# CSI2-TX2-XAVIER_Rev01.net
KiCad netlist of a schematic drawn in Altium Designer
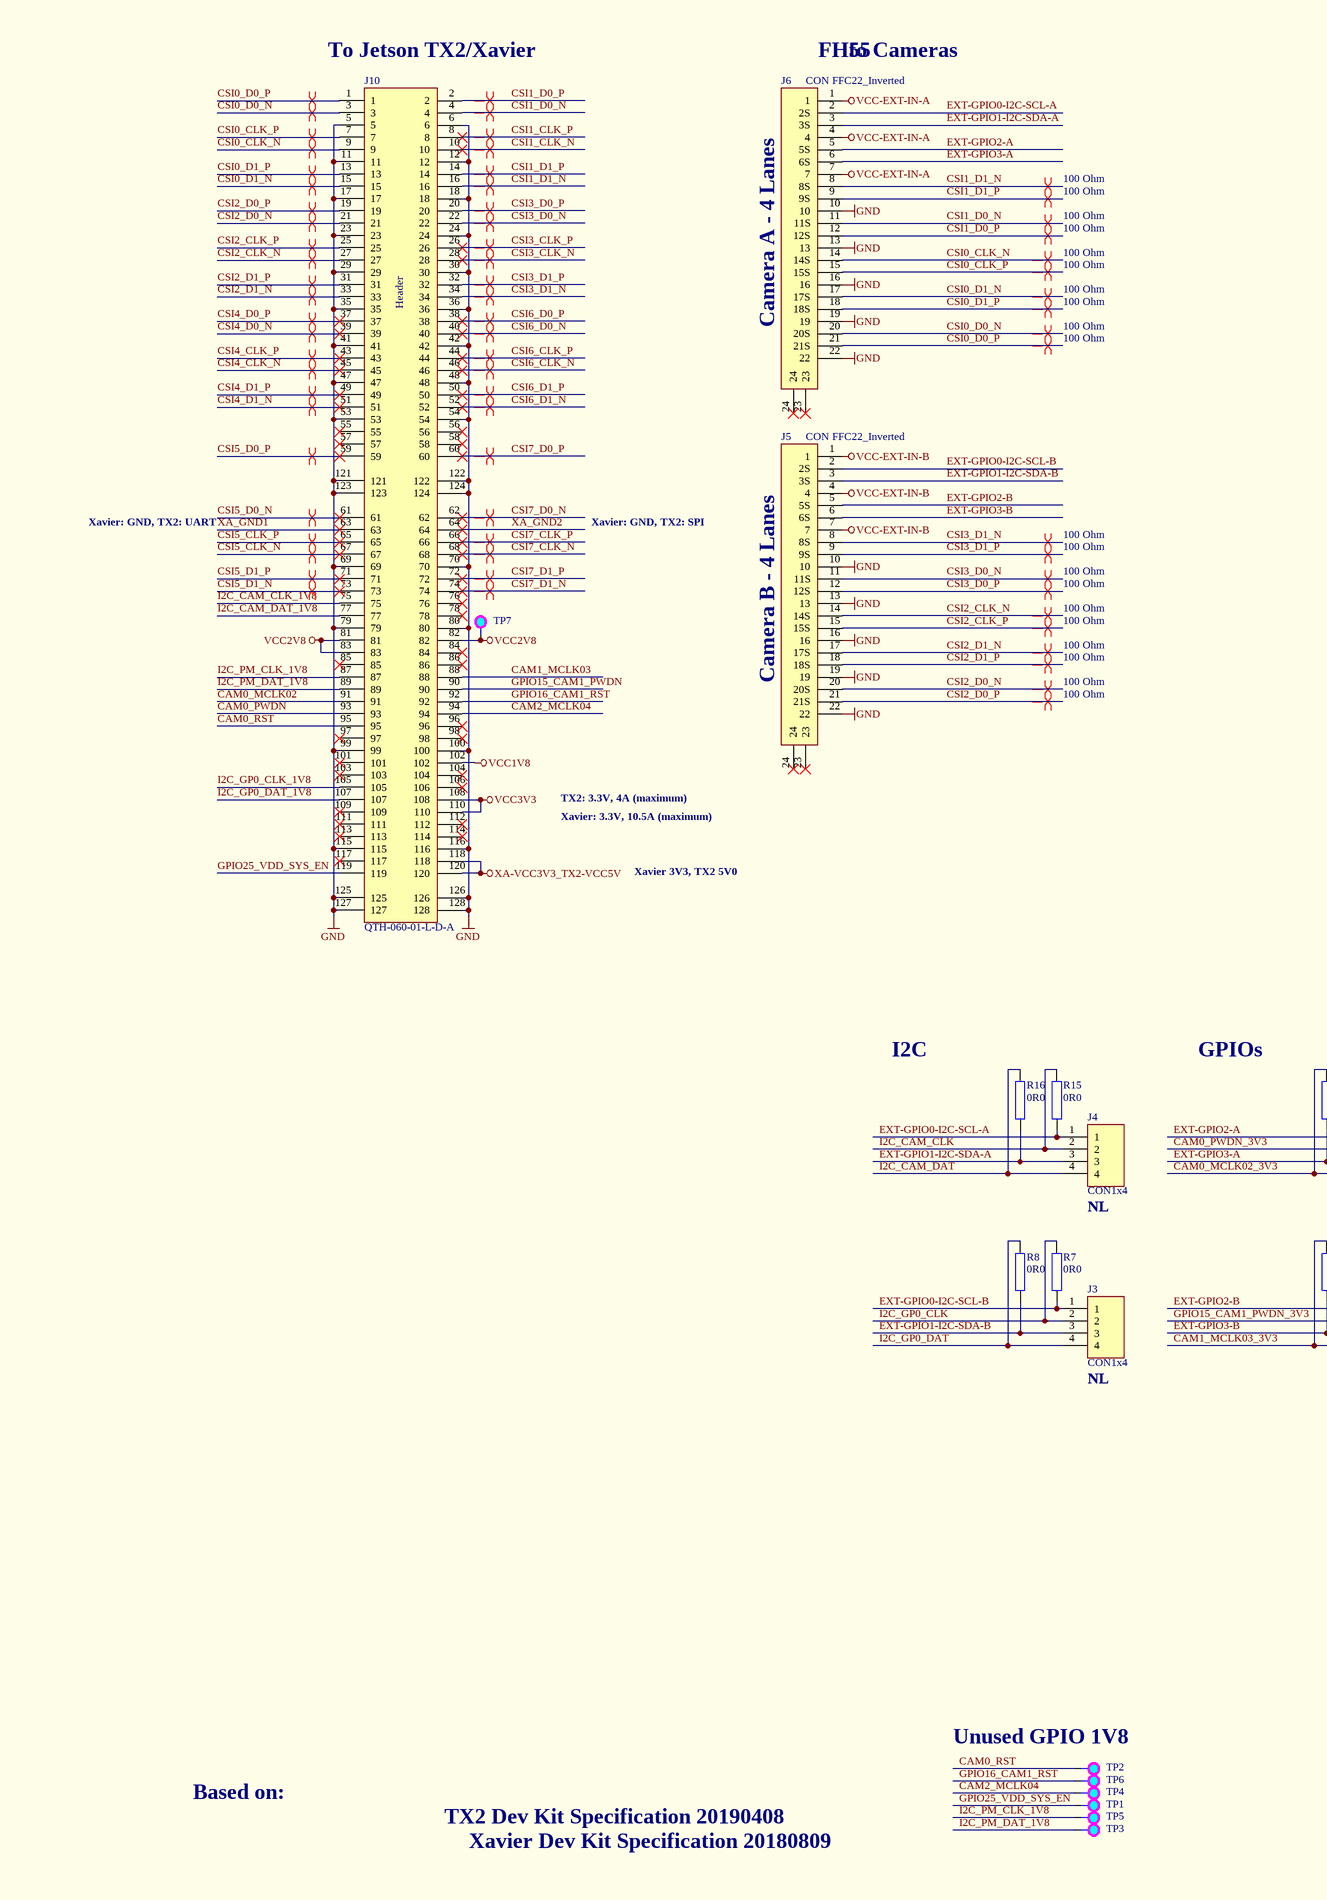
[diagram p0: CSI2-TX2-XAVIER_Rev01.SchDoc, left]
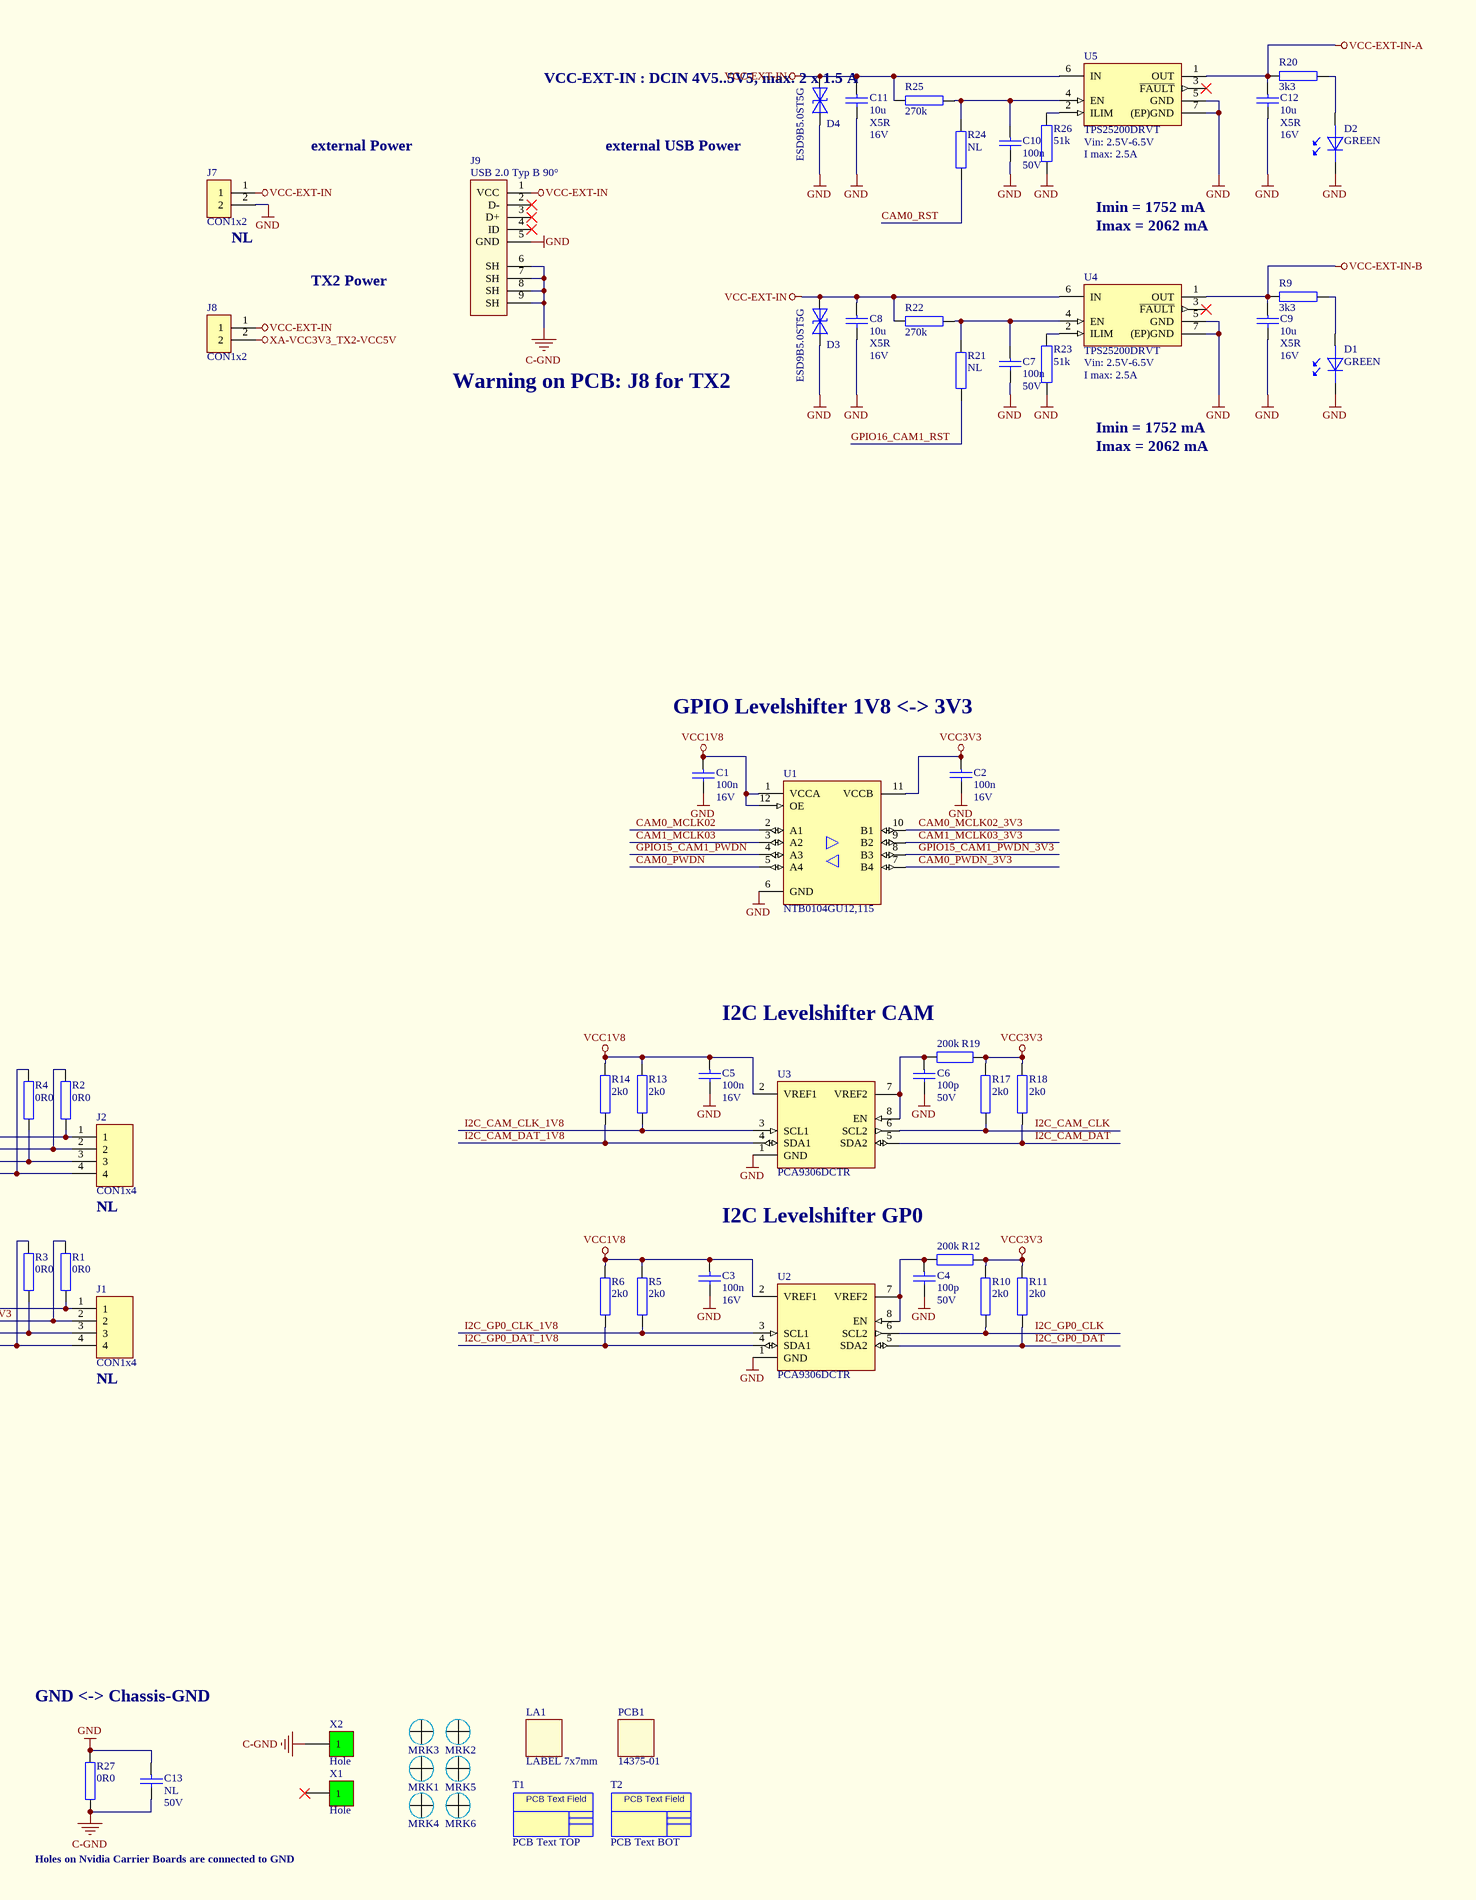
[diagram p1: CSI2-TX2-XAVIER_Rev01.SchDoc, right]

(export (version "E")
  (design (tool "Eeschema 10.0.6"))
  (components
    (comp (ref "C1")
      (value "100n")
      (footprint "C-0402_0.55")
      (description "Capacitor Ceramic SMD/0402/16V/X7R/10%")
      (fields
        (field (name "KHK PART NUMBER") "K8340114")
        (field (name "MANUFACTURER") "several")
        (field (name "VOLTAGE") "16V")
      )
      (libsource (lib "AVT_KHK_Lib") (part "C 100N 10% 16V X7R 402"))
    )
    (comp (ref "C2")
      (value "100n")
      (footprint "C-0402_0.55")
      (description "Capacitor Ceramic SMD/0402/16V/X7R/10%")
      (fields
        (field (name "KHK PART NUMBER") "K8340114")
        (field (name "MANUFACTURER") "several")
        (field (name "VOLTAGE") "16V")
      )
      (libsource (lib "AVT_KHK_Lib") (part "C 100N 10% 16V X7R 402"))
    )
    (comp (ref "C3")
      (value "100n")
      (footprint "C-0402_0.55")
      (description "Capacitor Ceramic SMD/0402/16V/X7R/10%")
      (fields
        (field (name "KHK PART NUMBER") "K8340114")
        (field (name "MANUFACTURER") "several")
        (field (name "VOLTAGE") "16V")
      )
      (libsource (lib "AVT_KHK_Lib") (part "C 100N 10% 16V X7R 402"))
    )
    (comp (ref "C4")
      (value "100p")
      (footprint "C-0402_0.55")
      (description "Capacitor Ceramic SMD/0402/50V/X7R/10%")
      (fields
        (field (name "KHK PART NUMBER") "K8340145")
        (field (name "MANUFACTURER") "several")
        (field (name "VOLTAGE") "50V")
      )
      (libsource (lib "AVT_KHK_Lib") (part "C 100P 50V X7R 0402"))
    )
    (comp (ref "C5")
      (value "100n")
      (footprint "C-0402_0.55")
      (description "Capacitor Ceramic SMD/0402/16V/X7R/10%")
      (fields
        (field (name "KHK PART NUMBER") "K8340114")
        (field (name "MANUFACTURER") "several")
        (field (name "VOLTAGE") "16V")
      )
      (libsource (lib "AVT_KHK_Lib") (part "C 100N 10% 16V X7R 402"))
    )
    (comp (ref "C6")
      (value "100p")
      (footprint "C-0402_0.55")
      (description "Capacitor Ceramic SMD/0402/50V/X7R/10%")
      (fields
        (field (name "KHK PART NUMBER") "K8340145")
        (field (name "MANUFACTURER") "several")
        (field (name "VOLTAGE") "50V")
      )
      (libsource (lib "AVT_KHK_Lib") (part "C 100P 50V X7R 0402"))
    )
    (comp (ref "C7")
      (value "100n")
      (footprint "C-0603_1.0")
      (description "Capacitor Ceramic SMD/0603/50V/X7R/10%")
      (fields
        (field (name "KHK PART NUMBER") "K8340023")
        (field (name "MANUFACTURER") "several")
        (field (name "VOLTAGE") "50V")
      )
      (libsource (lib "AVT_KHK_Lib") (part "C 100N 50V X7R 0603"))
    )
    (comp (ref "C8")
      (value "10u")
      (footprint "C-0805_1.4")
      (description "Capacitor Ceramic SMD/0805/16V/X5R/10%")
      (fields
        (field (name "KHK PART NUMBER") "K8340151")
        (field (name "MANUFACTURER") "several")
        (field (name "DIELECTRIC") "X5R")
        (field (name "VOLTAGE") "16V")
      )
      (libsource (lib "AVT_KHK_Lib") (part "C 10U 16V X5R 0805"))
    )
    (comp (ref "C9")
      (value "10u")
      (footprint "C-0805_1.4")
      (description "Capacitor Ceramic SMD/0805/16V/X5R/10%")
      (fields
        (field (name "KHK PART NUMBER") "K8340151")
        (field (name "MANUFACTURER") "several")
        (field (name "DIELECTRIC") "X5R")
        (field (name "VOLTAGE") "16V")
      )
      (libsource (lib "AVT_KHK_Lib") (part "C 10U 16V X5R 0805"))
    )
    (comp (ref "C10")
      (value "100n")
      (footprint "C-0603_1.0")
      (description "Capacitor Ceramic SMD/0603/50V/X7R/10%")
      (fields
        (field (name "KHK PART NUMBER") "K8340023")
        (field (name "MANUFACTURER") "several")
        (field (name "VOLTAGE") "50V")
      )
      (libsource (lib "AVT_KHK_Lib") (part "C 100N 50V X7R 0603"))
    )
    (comp (ref "C11")
      (value "10u")
      (footprint "C-0805_1.4")
      (description "Capacitor Ceramic SMD/0805/16V/X5R/10%")
      (fields
        (field (name "KHK PART NUMBER") "K8340151")
        (field (name "MANUFACTURER") "several")
        (field (name "DIELECTRIC") "X5R")
        (field (name "VOLTAGE") "16V")
      )
      (libsource (lib "AVT_KHK_Lib") (part "C 10U 16V X5R 0805"))
    )
    (comp (ref "C12")
      (value "10u")
      (footprint "C-0805_1.4")
      (description "Capacitor Ceramic SMD/0805/16V/X5R/10%")
      (fields
        (field (name "KHK PART NUMBER") "K8340151")
        (field (name "MANUFACTURER") "several")
        (field (name "DIELECTRIC") "X5R")
        (field (name "VOLTAGE") "16V")
      )
      (libsource (lib "AVT_KHK_Lib") (part "C 10U 16V X5R 0805"))
    )
    (comp (ref "C13")
      (value "NL")
      (footprint "C-0603_1.0")
      (description "Capacitor Ceramic SMD/0603/50V/X7R/10%")
      (fields
        (field (name "MANUFACTURER") "several")
        (field (name "TOLERANCE") "10%")
        (field (name "VOLTAGE") "50V")
      )
      (libsource (lib "AVT_KHK_Lib") (part "C X 0603"))
    )
    (comp (ref "D1")
      (value "GREEN")
      (footprint "D-0603-LED")
      (description "Chip LED green 430mcd")
      (fields (field (name "KHK PART NUMBER") "8172") (field (name "MANUFACTURER") "Würth"))
      (libsource (lib "AVT_KHK_Lib") (part "D LED 0603 green"))
    )
    (comp (ref "D2")
      (value "GREEN")
      (footprint "D-0603-LED")
      (description "Chip LED green 430mcd")
      (fields (field (name "KHK PART NUMBER") "8172") (field (name "MANUFACTURER") "Würth"))
      (libsource (lib "AVT_KHK_Lib") (part "D LED 0603 green"))
    )
    (comp (ref "D3")
      (value "ESD9B5.0ST5G")
      (footprint "D-SOD923")
      (description "DIODE TVS; 400W; 5.8-7.8V; BIDIRECT")
      (fields (field (name "KHK PART NUMBER") "7250") (field (name "MANUFACTURER") "ON Semiconductor"))
      (libsource (lib "AVT_KHK_Lib") (part "D ESD9B5.0ST5G"))
    )
    (comp (ref "D4")
      (value "ESD9B5.0ST5G")
      (footprint "D-SOD923")
      (description "DIODE TVS; 400W; 5.8-7.8V; BIDIRECT")
      (fields (field (name "KHK PART NUMBER") "7250") (field (name "MANUFACTURER") "ON Semiconductor"))
      (libsource (lib "AVT_KHK_Lib") (part "D ESD9B5.0ST5G"))
    )
    (comp (ref "J1")
      (value "CON1x4")
      (footprint "CON 1x4 RM2.54")
      (description "Stiftleiste; 1x4; 2.54mm; gerade")
      (fields (field (name "MANUFACTURER") "Harwin") (field (name "MANUFACTURER PART NUMBER") "M20-999 0445"))
      (libsource (lib "AVT_KHK_Lib") (part "CON 1x4 2.54"))
    )
    (comp (ref "J2")
      (value "CON1x4")
      (footprint "CON 1x4 RM2.54")
      (description "Stiftleiste; 1x4; 2.54mm; gerade")
      (fields (field (name "MANUFACTURER") "Harwin") (field (name "MANUFACTURER PART NUMBER") "M20-999 0445"))
      (libsource (lib "AVT_KHK_Lib") (part "CON 1x4 2.54"))
    )
    (comp (ref "J3")
      (value "CON1x4")
      (footprint "CON 1x4 RM2.54")
      (description "Stiftleiste; 1x4; 2.54mm; gerade")
      (fields (field (name "MANUFACTURER") "Harwin") (field (name "MANUFACTURER PART NUMBER") "M20-999 0445"))
      (libsource (lib "AVT_KHK_Lib") (part "CON 1x4 2.54"))
    )
    (comp (ref "J4")
      (value "CON1x4")
      (footprint "CON 1x4 RM2.54")
      (description "Stiftleiste; 1x4; 2.54mm; gerade")
      (fields (field (name "MANUFACTURER") "Harwin") (field (name "MANUFACTURER PART NUMBER") "M20-999 0445"))
      (libsource (lib "AVT_KHK_Lib") (part "CON 1x4 2.54"))
    )
    (comp (ref "J5")
      (value "CON FFC22_Inverted")
      (footprint "J-FH55-22S-0.5SH - Inverted Pins")
      (description "FFC Connector 0.5mm shielded")
      (fields
        (field (name "KHK PART NUMBER") "10357")
        (field (name "MANUFACTURER PART NUMBER") "FH55-22S-0.5SH")
      )
      (libsource (lib "AVT_KHK_Lib") (part "CON FFC22_FH55-22S-0.5SH_Inverted"))
    )
    (comp (ref "J6")
      (value "CON FFC22_Inverted")
      (footprint "J-FH55-22S-0.5SH - Inverted Pins")
      (description "FFC Connector 0.5mm shielded")
      (fields
        (field (name "KHK PART NUMBER") "10357")
        (field (name "MANUFACTURER PART NUMBER") "FH55-22S-0.5SH")
      )
      (libsource (lib "AVT_KHK_Lib") (part "CON FFC22_FH55-22S-0.5SH_Inverted"))
    )
    (comp (ref "J7")
      (value "CON1x2")
      (footprint "CON 1x2 RM2.54")
      (description "Stiftleiste; 1x2; 2.54mm; gerade")
      (fields
        (field (name "MANUFACTURER") "fischer elektronik")
        (field (name "MANUFACTURER PART NUMBER") "SL 11 124 2 G")
      )
      (libsource (lib "AVT_KHK_Lib") (part "CON 1x2 2.54"))
    )
    (comp (ref "J8")
      (value "CON1x2")
      (footprint "CON 1x2 RM2.54")
      (description "Stiftleiste; 1x2; 2.54mm; gerade")
      (fields
        (field (name "MANUFACTURER") "fischer elektronik")
        (field (name "MANUFACTURER PART NUMBER") "SL 11 124 2 G")
      )
      (libsource (lib "AVT_KHK_Lib") (part "CON 1x2 2.54"))
    )
    (comp (ref "J9")
      (value "USB 2.0 Typ B 90°")
      (footprint "J-629105150521")
      (description "Micro USB 2.0 Typ B 90°")
      (fields (field (name "KHK PART NUMBER") "14360") (field (name "MANUFACTURER") "WE"))
      (libsource (lib "Connector") (part "CON USB 2.0 Typ B 90°"))
    )
    (comp (ref "J10")
      (value "QTH-060-01-L-D-A")
      (footprint "J-QTH-060-XX-X-D-A")
      (description "120pin B2B Header 0.5 pitch 10.27mm Height")
      (fields (field (name "MANUFACTURER") "SamTec") (field (name "KHK PART NUMBER") "10657"))
      (libsource (lib "AVT_KHK_Lib") (part "CON QTH-060-01-L-D-A"))
    )
    (comp (ref "LA1")
      (value "LABEL 7x7mm")
      (footprint "PCB LABEL 7x7")
      (fields (field (name "MANUFACTURER") "several"))
      (libsource (lib "AVT_KHK_Lib") (part "PCB LABEL 7x7"))
    )
    (comp (ref "MRK1")
      (value "Marker Single Layer")
      (footprint "PCB_Marker_Pad_top")
      (description "Position Marker for PCBs")
      (libsource (lib "AVT_KHK_Lib") (part "PCB Marker Pad Single Layer"))
    )
    (comp (ref "MRK2")
      (value "Marker Single Layer")
      (footprint "PCB_Marker_Pad_top")
      (description "Position Marker for PCBs")
      (libsource (lib "AVT_KHK_Lib") (part "PCB Marker Pad Single Layer"))
    )
    (comp (ref "MRK3")
      (value "Marker Single Layer")
      (footprint "PCB_Marker_Pad_top")
      (description "Position Marker for PCBs")
      (libsource (lib "AVT_KHK_Lib") (part "PCB Marker Pad Single Layer"))
    )
    (comp (ref "MRK4")
      (value "Marker Single Layer")
      (footprint "PCB_Marker_Pad_top")
      (description "Position Marker for PCBs")
      (libsource (lib "AVT_KHK_Lib") (part "PCB Marker Pad Single Layer"))
    )
    (comp (ref "MRK5")
      (value "Marker Single Layer")
      (footprint "PCB_Marker_Pad_top")
      (description "Position Marker for PCBs")
      (libsource (lib "AVT_KHK_Lib") (part "PCB Marker Pad Single Layer"))
    )
    (comp (ref "MRK6")
      (value "Marker Single Layer")
      (footprint "PCB_Marker_Pad_top")
      (description "Position Marker for PCBs")
      (libsource (lib "AVT_KHK_Lib") (part "PCB Marker Pad Single Layer"))
    )
    (comp (ref "PCB1")
      (value "14375-01")
      (description "PCB ML04")
      (fields (field (name "MANUFACTURER") "several"))
      (libsource (lib "AVT_KHK_Lib") (part "PCB"))
    )
    (comp (ref "R1")
      (value "0R0")
      (footprint "R-0603_0.6")
      (description "Standard Resistor SMD/0603/1%/100mW/TK200")
      (fields (field (name "KHK PART NUMBER") "K8250041") (field (name "MANUFACTURER") "several"))
      (libsource (lib "AVT_KHK_Lib") (part "R 0R0 1% 0603"))
    )
    (comp (ref "R2")
      (value "0R0")
      (footprint "R-0603_0.6")
      (description "Standard Resistor SMD/0603/1%/100mW/TK200")
      (fields (field (name "KHK PART NUMBER") "K8250041") (field (name "MANUFACTURER") "several"))
      (libsource (lib "AVT_KHK_Lib") (part "R 0R0 1% 0603"))
    )
    (comp (ref "R3")
      (value "0R0")
      (footprint "R-0603_0.6")
      (description "Standard Resistor SMD/0603/1%/100mW/TK200")
      (fields (field (name "KHK PART NUMBER") "K8250041") (field (name "MANUFACTURER") "several"))
      (libsource (lib "AVT_KHK_Lib") (part "R 0R0 1% 0603"))
    )
    (comp (ref "R4")
      (value "0R0")
      (footprint "R-0603_0.6")
      (description "Standard Resistor SMD/0603/1%/100mW/TK200")
      (fields (field (name "KHK PART NUMBER") "K8250041") (field (name "MANUFACTURER") "several"))
      (libsource (lib "AVT_KHK_Lib") (part "R 0R0 1% 0603"))
    )
    (comp (ref "R5")
      (value "2k0")
      (footprint "R-0402_0.4")
      (description "Standard Resistor SMD/0402/1%/63mW/TK100")
      (fields (field (name "KHK PART NUMBER") "K8250311") (field (name "MANUFACTURER") "several"))
      (libsource (lib "AVT_KHK_Lib") (part "R 2k0 1% 0402"))
    )
    (comp (ref "R6")
      (value "2k0")
      (footprint "R-0402_0.4")
      (description "Standard Resistor SMD/0402/1%/63mW/TK100")
      (fields (field (name "KHK PART NUMBER") "K8250311") (field (name "MANUFACTURER") "several"))
      (libsource (lib "AVT_KHK_Lib") (part "R 2k0 1% 0402"))
    )
    (comp (ref "R7")
      (value "0R0")
      (footprint "R-0603_0.6")
      (description "Standard Resistor SMD/0603/1%/100mW/TK100")
      (fields (field (name "KHK PART NUMBER") "K8250041") (field (name "MANUFACTURER") "several"))
      (libsource (lib "AVT_KHK_Lib") (part "R 0R0 1% 0603"))
    )
    (comp (ref "R8")
      (value "0R0")
      (footprint "R-0603_0.6")
      (description "Standard Resistor SMD/0603/1%/100mW/TK100")
      (fields (field (name "KHK PART NUMBER") "K8250041") (field (name "MANUFACTURER") "several"))
      (libsource (lib "AVT_KHK_Lib") (part "R 0R0 1% 0603"))
    )
    (comp (ref "R9")
      (value "3k3")
      (footprint "R-0603_0.6")
      (description "Standard Resistor SMD/0603/1%/100mW/TK100")
      (fields (field (name "KHK PART NUMBER") "K8250070") (field (name "MANUFACTURER") "several"))
      (libsource (lib "AVT_KHK_Lib") (part "R 3K3 1% 0603"))
    )
    (comp (ref "R10")
      (value "2k0")
      (footprint "R-0402_0.4")
      (description "Standard Resistor SMD/0402/1%/63mW/TK100")
      (fields (field (name "KHK PART NUMBER") "K8250311") (field (name "MANUFACTURER") "several"))
      (libsource (lib "AVT_KHK_Lib") (part "R 2k0 1% 0402"))
    )
    (comp (ref "R11")
      (value "2k0")
      (footprint "R-0402_0.4")
      (description "Standard Resistor SMD/0402/1%/63mW/TK100")
      (fields (field (name "KHK PART NUMBER") "K8250311") (field (name "MANUFACTURER") "several"))
      (libsource (lib "AVT_KHK_Lib") (part "R 2k0 1% 0402"))
    )
    (comp (ref "R12")
      (value "200k")
      (footprint "R-0402_0.4")
      (description "Standard Resistor SMD/0402/1%/63mW/TK100")
      (fields (field (name "KHK PART NUMBER") "K8250280") (field (name "MANUFACTURER") "several"))
      (libsource (lib "AVT_KHK_Lib") (part "R 200K 1% 0402"))
    )
    (comp (ref "R13")
      (value "2k0")
      (footprint "R-0402_0.4")
      (description "Standard Resistor SMD/0402/1%/63mW/TK100")
      (fields (field (name "KHK PART NUMBER") "K8250311") (field (name "MANUFACTURER") "several"))
      (libsource (lib "AVT_KHK_Lib") (part "R 2k0 1% 0402"))
    )
    (comp (ref "R14")
      (value "2k0")
      (footprint "R-0402_0.4")
      (description "Standard Resistor SMD/0402/1%/63mW/TK100")
      (fields (field (name "KHK PART NUMBER") "K8250311") (field (name "MANUFACTURER") "several"))
      (libsource (lib "AVT_KHK_Lib") (part "R 2k0 1% 0402"))
    )
    (comp (ref "R15")
      (value "0R0")
      (footprint "R-0603_0.6")
      (description "Standard Resistor SMD/0603/1%/100mW/TK100")
      (fields (field (name "KHK PART NUMBER") "K8250041") (field (name "MANUFACTURER") "several"))
      (libsource (lib "AVT_KHK_Lib") (part "R 0R0 1% 0603"))
    )
    (comp (ref "R16")
      (value "0R0")
      (footprint "R-0603_0.6")
      (description "Standard Resistor SMD/0603/1%/100mW/TK100")
      (fields (field (name "KHK PART NUMBER") "K8250041") (field (name "MANUFACTURER") "several"))
      (libsource (lib "AVT_KHK_Lib") (part "R 0R0 1% 0603"))
    )
    (comp (ref "R17")
      (value "2k0")
      (footprint "R-0402_0.4")
      (description "Standard Resistor SMD/0402/1%/63mW/TK100")
      (fields (field (name "KHK PART NUMBER") "K8250311") (field (name "MANUFACTURER") "several"))
      (libsource (lib "AVT_KHK_Lib") (part "R 2k0 1% 0402"))
    )
    (comp (ref "R18")
      (value "2k0")
      (footprint "R-0402_0.4")
      (description "Standard Resistor SMD/0402/1%/63mW/TK100")
      (fields (field (name "KHK PART NUMBER") "K8250311") (field (name "MANUFACTURER") "several"))
      (libsource (lib "AVT_KHK_Lib") (part "R 2k0 1% 0402"))
    )
    (comp (ref "R19")
      (value "200k")
      (footprint "R-0402_0.4")
      (description "Standard Resistor SMD/0402/1%/63mW/TK100")
      (fields (field (name "KHK PART NUMBER") "K8250280") (field (name "MANUFACTURER") "several"))
      (libsource (lib "AVT_KHK_Lib") (part "R 200K 1% 0402"))
    )
    (comp (ref "R20")
      (value "3k3")
      (footprint "R-0603_0.6")
      (description "Standard Resistor SMD/0603/1%/100mW/TK100")
      (fields (field (name "KHK PART NUMBER") "K8250070") (field (name "MANUFACTURER") "several"))
      (libsource (lib "AVT_KHK_Lib") (part "R 3K3 1% 0603"))
    )
    (comp (ref "R21")
      (value "NL")
      (footprint "R-0603_0.6")
      (description "Standard Resistor SMD/0603/1%/100mW/TK200")
      (fields (field (name "TOLERANCE") "1%"))
      (libsource (lib "AVT_KHK_Lib") (part "R X 0603"))
    )
    (comp (ref "R22")
      (value "270k")
      (footprint "R-0603_0.6")
      (description "Standard Resistor SMD/0603/1%/100mW/TK100")
      (fields (field (name "KHK PART NUMBER") "K8250170") (field (name "MANUFACTURER") "several"))
      (libsource (lib "AVT_KHK_Lib") (part "R 270K 1% 0603"))
    )
    (comp (ref "R23")
      (value "51k")
      (footprint "R-0603_0.6")
      (description "Standard Resistor SMD/0603/1%/100mW/TK100")
      (fields (field (name "KHK PART NUMBER") "K8250156") (field (name "MANUFACTURER") "several"))
      (libsource (lib "AVT_KHK_Lib") (part "R 51K 1% 0603"))
    )
    (comp (ref "R24")
      (value "NL")
      (footprint "R-0603_0.6")
      (description "Standard Resistor SMD/0603/1%/100mW/TK200")
      (fields (field (name "TOLERANCE") "1%"))
      (libsource (lib "AVT_KHK_Lib") (part "R X 0603"))
    )
    (comp (ref "R25")
      (value "270k")
      (footprint "R-0603_0.6")
      (description "Standard Resistor SMD/0603/1%/100mW/TK100")
      (fields (field (name "KHK PART NUMBER") "K8250170") (field (name "MANUFACTURER") "several"))
      (libsource (lib "AVT_KHK_Lib") (part "R 270K 1% 0603"))
    )
    (comp (ref "R26")
      (value "51k")
      (footprint "R-0603_0.6")
      (description "Standard Resistor SMD/0603/1%/100mW/TK100")
      (fields (field (name "KHK PART NUMBER") "K8250156") (field (name "MANUFACTURER") "several"))
      (libsource (lib "AVT_KHK_Lib") (part "R 51K 1% 0603"))
    )
    (comp (ref "R27")
      (value "0R0")
      (footprint "R-0603_0.6")
      (description "Standard Resistor SMD/0603/1%/100mW/TK200")
      (fields (field (name "KHK PART NUMBER") "K8250041") (field (name "MANUFACTURER") "several"))
      (libsource (lib "AVT_KHK_Lib") (part "R 0R0 1% 0603"))
    )
    (comp (ref "T1")
      (value "PCB Text TOP")
      (footprint "PCB TEXTFIELD TOP 2")
      (description "PCB Textfield TOP")
      (libsource (lib "AVT_KHK_Lib") (part "PCB TEXT FIELD TOP"))
    )
    (comp (ref "T2")
      (value "PCB Text BOT")
      (footprint "PCB TEXTFIELD BOT 2")
      (description "PCB Textfield BOT")
      (libsource (lib "AVT_KHK_Lib") (part "PCB TEXT FIELD BOT"))
    )
    (comp (ref "TP1")
      (value "TP")
      (footprint "TP_16_10")
      (description "Testpoint: Pad=1,6mm; Hole=1,0mm")
      (libsource (lib "AVT_KHK_Lib") (part "TP_16_10"))
    )
    (comp (ref "TP2")
      (value "TP")
      (footprint "TP_16_10")
      (description "Testpoint: Pad=1,6mm; Hole=1,0mm")
      (libsource (lib "AVT_KHK_Lib") (part "TP_16_10"))
    )
    (comp (ref "TP3")
      (value "TP")
      (footprint "TP_16_10")
      (description "Testpoint: Pad=1,6mm; Hole=1,0mm")
      (libsource (lib "AVT_KHK_Lib") (part "TP_16_10"))
    )
    (comp (ref "TP4")
      (value "TP")
      (footprint "TP_16_10")
      (description "Testpoint: Pad=1,6mm; Hole=1,0mm")
      (libsource (lib "AVT_KHK_Lib") (part "TP_16_10"))
    )
    (comp (ref "TP5")
      (value "TP")
      (footprint "TP_16_10")
      (description "Testpoint: Pad=1,6mm; Hole=1,0mm")
      (libsource (lib "AVT_KHK_Lib") (part "TP_16_10"))
    )
    (comp (ref "TP6")
      (value "TP")
      (footprint "TP_16_10")
      (description "Testpoint: Pad=1,6mm; Hole=1,0mm")
      (libsource (lib "AVT_KHK_Lib") (part "TP_16_10"))
    )
    (comp (ref "TP7")
      (value "TP")
      (footprint "TP_16_10")
      (description "Testpoint: Pad=1,6mm; Hole=1,0mm")
      (libsource (lib "AVT_KHK_Lib") (part "TP_16_10"))
    )
    (comp (ref "U1")
      (value "NTB0104GU12,115")
      (footprint "IC-XQFN12_1.7x2x0.5")
      (description "IC/LOGIC/Levelshifter;Auto-Dir;Bidirectional;Push-Pull;-40-+125°C/")
      (fields (field (name "MANUFACTURER") "NXP") (field (name "KHK PART NUMBER") "14383"))
      (libsource (lib "AVT_KHK_Lib") (part "IC NTB0104GU12,115"))
    )
    (comp (ref "U2")
      (value "PCA9306DCTR")
      (footprint "IC-TSSOP8_3.15x4.25x1.3")
      (description "IC/LOGIC/LEVELSHIFTER;I2C;AUTO-DIR;1V2-5V/SSOP-8/4.25x3.15x1.3mm")
      (fields (field (name "KHK PART NUMBER") "9555") (field (name "MANUFACTURER") "TI"))
      (libsource (lib "AVT_KHK_Lib") (part "IC PCA9306DCTR"))
    )
    (comp (ref "U3")
      (value "PCA9306DCTR")
      (footprint "IC-TSSOP8_3.15x4.25x1.3")
      (description "IC/LOGIC/LEVELSHIFTER;I2C;AUTO-DIR;1V2-5V/SSOP-8/4.25x3.15x1.3mm")
      (fields (field (name "KHK PART NUMBER") "9555") (field (name "MANUFACTURER") "TI"))
      (libsource (lib "AVT_KHK_Lib") (part "IC PCA9306DCTR"))
    )
    (comp (ref "U4")
      (value "TPS25200DRVT")
      (footprint "IC-DFN06_2.0x2.0x0.8")
      (description "IC/PWR/LOADSW;2V5-6V5;2A5;0R099/6-WDFN/2x2x0.8mm")
      (fields
        (field (name "KHK PART NUMBER") "14277")
        (field (name "MANUFACTURER") "Texas Instruments")
        (field (name "VIN") "2.5V-6.5V")
        (field (name "I MAX") "2.5A")
      )
      (libsource (lib "AVT_KHK_Lib") (part "IC  TPS25200DRVT"))
    )
    (comp (ref "U5")
      (value "TPS25200DRVT")
      (footprint "IC-DFN06_2.0x2.0x0.8")
      (description "IC/PWR/LOADSW;2V5-6V5;2A5;0R099/6-WDFN/2x2x0.8mm")
      (fields
        (field (name "KHK PART NUMBER") "14277")
        (field (name "MANUFACTURER") "Texas Instruments")
        (field (name "VIN") "2.5V-6.5V")
        (field (name "I MAX") "2.5A")
      )
      (libsource (lib "AVT_KHK_Lib") (part "IC  TPS25200DRVT"))
    )
    (comp (ref "X1")
      (value "Hole")
      (footprint "HOLE-3.2-6.0-DK")
      (description "HOLE M3")
      (libsource (lib "AVT_KHK_Lib") (part "PCB HOLE M3-6-DK"))
    )
    (comp (ref "X2")
      (value "Hole")
      (footprint "HOLE-3.2-6.0-DK")
      (description "HOLE M3")
      (libsource (lib "AVT_KHK_Lib") (part "PCB HOLE M3-6-DK"))
    )
  )
  (nets
    (net (code "1") (name "/CAM0_MCLK02") (class "Default")
      (node (ref "J10") (pin "91") (pinfunction "91_91") (pintype "passive"))
      (node (ref "U1") (pin "2") (pinfunction "A1_2") (pintype "bidirectional"))
    )
    (net (code "2") (name "/CAM0_MCLK02_3V3") (class "Default")
      (node (ref "J2") (pin "4") (pinfunction "4_4") (pintype "passive"))
      (node (ref "R4") (pin "2") (pinfunction "2_2") (pintype "passive"))
      (node (ref "U1") (pin "10") (pinfunction "B1_10") (pintype "bidirectional"))
    )
    (net (code "3") (name "/CAM0_PWDN") (class "Default")
      (node (ref "J10") (pin "93") (pinfunction "93_93") (pintype "passive"))
      (node (ref "U1") (pin "5") (pinfunction "A4_5") (pintype "bidirectional"))
    )
    (net (code "4") (name "/CAM0_PWDN_3V3") (class "Default")
      (node (ref "J2") (pin "2") (pinfunction "2_2") (pintype "passive"))
      (node (ref "R2") (pin "2") (pinfunction "2_2") (pintype "passive"))
      (node (ref "U1") (pin "7") (pinfunction "B4_7") (pintype "bidirectional"))
    )
    (net (code "5") (name "/CAM0_RST") (class "Default")
      (node (ref "J10") (pin "95") (pinfunction "95_95") (pintype "passive"))
      (node (ref "R24") (pin "1") (pinfunction "1_1") (pintype "passive"))
      (node (ref "TP2") (pin "1") (pinfunction "1_1") (pintype "passive"))
    )
    (net (code "6") (name "/CAM1_MCLK03") (class "Default")
      (node (ref "J10") (pin "88") (pinfunction "88_88") (pintype "passive"))
      (node (ref "U1") (pin "3") (pinfunction "A2_3") (pintype "bidirectional"))
    )
    (net (code "7") (name "/CAM1_MCLK03_3V3") (class "Default")
      (node (ref "J1") (pin "4") (pinfunction "4_4") (pintype "passive"))
      (node (ref "R3") (pin "2") (pinfunction "2_2") (pintype "passive"))
      (node (ref "U1") (pin "9") (pinfunction "B2_9") (pintype "bidirectional"))
    )
    (net (code "8") (name "/CAM2_MCLK04") (class "Default")
      (node (ref "J10") (pin "94") (pinfunction "94_94") (pintype "passive"))
      (node (ref "TP4") (pin "1") (pinfunction "1_1") (pintype "passive"))
    )
    (net (code "9") (name "/CSI0_CLK_N") (class "Default")
      (node (ref "J10") (pin "9") (pinfunction "9_9") (pintype "passive"))
      (node (ref "J6") (pin "14") (pinfunction "14S_14") (pintype "passive"))
    )
    (net (code "10") (name "/CSI0_CLK_P") (class "Default")
      (node (ref "J10") (pin "7") (pinfunction "7_7") (pintype "passive"))
      (node (ref "J6") (pin "15") (pinfunction "15S_15") (pintype "passive"))
    )
    (net (code "11") (name "/CSI0_D0_N") (class "Default")
      (node (ref "J10") (pin "3") (pinfunction "3_3") (pintype "passive"))
      (node (ref "J6") (pin "20") (pinfunction "20S_20") (pintype "passive"))
    )
    (net (code "12") (name "/CSI0_D0_P") (class "Default")
      (node (ref "J10") (pin "1") (pinfunction "1_1") (pintype "passive"))
      (node (ref "J6") (pin "21") (pinfunction "21S_21") (pintype "passive"))
    )
    (net (code "13") (name "/CSI0_D1_N") (class "Default")
      (node (ref "J10") (pin "15") (pinfunction "15_15") (pintype "passive"))
      (node (ref "J6") (pin "17") (pinfunction "17S_17") (pintype "passive"))
    )
    (net (code "14") (name "/CSI0_D1_P") (class "Default")
      (node (ref "J10") (pin "13") (pinfunction "13_13") (pintype "passive"))
      (node (ref "J6") (pin "18") (pinfunction "18S_18") (pintype "passive"))
    )
    (net (code "15") (name "/CSI1_CLK_N") (class "Default")
      (node (ref "J10") (pin "10") (pinfunction "10_10") (pintype "passive+no_connect"))
    )
    (net (code "16") (name "/CSI1_CLK_P") (class "Default")
      (node (ref "J10") (pin "8") (pinfunction "8_8") (pintype "passive+no_connect"))
    )
    (net (code "17") (name "/CSI1_D0_N") (class "Default")
      (node (ref "J10") (pin "4") (pinfunction "4_4") (pintype "passive"))
      (node (ref "J6") (pin "11") (pinfunction "11S_11") (pintype "passive"))
    )
    (net (code "18") (name "/CSI1_D0_P") (class "Default")
      (node (ref "J10") (pin "2") (pinfunction "2_2") (pintype "passive"))
      (node (ref "J6") (pin "12") (pinfunction "12S_12") (pintype "passive"))
    )
    (net (code "19") (name "/CSI1_D1_N") (class "Default")
      (node (ref "J10") (pin "16") (pinfunction "16_16") (pintype "passive"))
      (node (ref "J6") (pin "8") (pinfunction "8S_8") (pintype "passive"))
    )
    (net (code "20") (name "/CSI1_D1_P") (class "Default")
      (node (ref "J10") (pin "14") (pinfunction "14_14") (pintype "passive"))
      (node (ref "J6") (pin "9") (pinfunction "9S_9") (pintype "passive"))
    )
    (net (code "21") (name "/CSI2_CLK_N") (class "Default")
      (node (ref "J10") (pin "27") (pinfunction "27_27") (pintype "passive"))
      (node (ref "J5") (pin "14") (pinfunction "14S_14") (pintype "passive"))
    )
    (net (code "22") (name "/CSI2_CLK_P") (class "Default")
      (node (ref "J10") (pin "25") (pinfunction "25_25") (pintype "passive"))
      (node (ref "J5") (pin "15") (pinfunction "15S_15") (pintype "passive"))
    )
    (net (code "23") (name "/CSI2_D0_N") (class "Default")
      (node (ref "J10") (pin "21") (pinfunction "21_21") (pintype "passive"))
      (node (ref "J5") (pin "20") (pinfunction "20S_20") (pintype "passive"))
    )
    (net (code "24") (name "/CSI2_D0_P") (class "Default")
      (node (ref "J10") (pin "19") (pinfunction "19_19") (pintype "passive"))
      (node (ref "J5") (pin "21") (pinfunction "21S_21") (pintype "passive"))
    )
    (net (code "25") (name "/CSI2_D1_N") (class "Default")
      (node (ref "J10") (pin "33") (pinfunction "33_33") (pintype "passive"))
      (node (ref "J5") (pin "17") (pinfunction "17S_17") (pintype "passive"))
    )
    (net (code "26") (name "/CSI2_D1_P") (class "Default")
      (node (ref "J10") (pin "31") (pinfunction "31_31") (pintype "passive"))
      (node (ref "J5") (pin "18") (pinfunction "18S_18") (pintype "passive"))
    )
    (net (code "27") (name "/CSI3_CLK_N") (class "Default")
      (node (ref "J10") (pin "28") (pinfunction "28_28") (pintype "passive+no_connect"))
    )
    (net (code "28") (name "/CSI3_CLK_P") (class "Default")
      (node (ref "J10") (pin "26") (pinfunction "26_26") (pintype "passive+no_connect"))
    )
    (net (code "29") (name "/CSI3_D0_N") (class "Default")
      (node (ref "J10") (pin "22") (pinfunction "22_22") (pintype "passive"))
      (node (ref "J5") (pin "11") (pinfunction "11S_11") (pintype "passive"))
    )
    (net (code "30") (name "/CSI3_D0_P") (class "Default")
      (node (ref "J10") (pin "20") (pinfunction "20_20") (pintype "passive"))
      (node (ref "J5") (pin "12") (pinfunction "12S_12") (pintype "passive"))
    )
    (net (code "31") (name "/CSI3_D1_N") (class "Default")
      (node (ref "J10") (pin "34") (pinfunction "34_34") (pintype "passive"))
      (node (ref "J5") (pin "8") (pinfunction "8S_8") (pintype "passive"))
    )
    (net (code "32") (name "/CSI3_D1_P") (class "Default")
      (node (ref "J10") (pin "32") (pinfunction "32_32") (pintype "passive"))
      (node (ref "J5") (pin "9") (pinfunction "9S_9") (pintype "passive"))
    )
    (net (code "33") (name "/CSI4_CLK_N") (class "Default")
      (node (ref "J10") (pin "45") (pinfunction "45_45") (pintype "passive+no_connect"))
    )
    (net (code "34") (name "/CSI4_CLK_P") (class "Default")
      (node (ref "J10") (pin "43") (pinfunction "43_43") (pintype "passive+no_connect"))
    )
    (net (code "35") (name "/CSI4_D0_N") (class "Default")
      (node (ref "J10") (pin "39") (pinfunction "39_39") (pintype "passive+no_connect"))
    )
    (net (code "36") (name "/CSI4_D0_P") (class "Default")
      (node (ref "J10") (pin "37") (pinfunction "37_37") (pintype "passive+no_connect"))
    )
    (net (code "37") (name "/CSI4_D1_N") (class "Default")
      (node (ref "J10") (pin "51") (pinfunction "51_51") (pintype "passive+no_connect"))
    )
    (net (code "38") (name "/CSI4_D1_P") (class "Default")
      (node (ref "J10") (pin "49") (pinfunction "49_49") (pintype "passive+no_connect"))
    )
    (net (code "39") (name "/CSI5_CLK_N") (class "Default")
      (node (ref "J10") (pin "67") (pinfunction "67_67") (pintype "passive+no_connect"))
    )
    (net (code "40") (name "/CSI5_CLK_P") (class "Default")
      (node (ref "J10") (pin "65") (pinfunction "65_65") (pintype "passive+no_connect"))
    )
    (net (code "41") (name "/CSI5_D0_N") (class "Default")
      (node (ref "J10") (pin "61") (pinfunction "61_61") (pintype "passive+no_connect"))
    )
    (net (code "42") (name "/CSI5_D0_P") (class "Default")
      (node (ref "J10") (pin "59") (pinfunction "59_59") (pintype "passive+no_connect"))
    )
    (net (code "43") (name "/CSI5_D1_N") (class "Default")
      (node (ref "J10") (pin "73") (pinfunction "73_73") (pintype "passive+no_connect"))
    )
    (net (code "44") (name "/CSI5_D1_P") (class "Default")
      (node (ref "J10") (pin "71") (pinfunction "71_71") (pintype "passive+no_connect"))
    )
    (net (code "45") (name "/CSI6_CLK_N") (class "Default")
      (node (ref "J10") (pin "46") (pinfunction "46_46") (pintype "passive+no_connect"))
    )
    (net (code "46") (name "/CSI6_CLK_P") (class "Default")
      (node (ref "J10") (pin "44") (pinfunction "44_44") (pintype "passive+no_connect"))
    )
    (net (code "47") (name "/CSI6_D0_N") (class "Default")
      (node (ref "J10") (pin "40") (pinfunction "40_40") (pintype "passive+no_connect"))
    )
    (net (code "48") (name "/CSI6_D0_P") (class "Default")
      (node (ref "J10") (pin "38") (pinfunction "38_38") (pintype "passive+no_connect"))
    )
    (net (code "49") (name "/CSI6_D1_N") (class "Default")
      (node (ref "J10") (pin "52") (pinfunction "52_52") (pintype "passive+no_connect"))
    )
    (net (code "50") (name "/CSI6_D1_P") (class "Default")
      (node (ref "J10") (pin "50") (pinfunction "50_50") (pintype "passive+no_connect"))
    )
    (net (code "51") (name "/CSI7_CLK_N") (class "Default")
      (node (ref "J10") (pin "68") (pinfunction "68_68") (pintype "passive+no_connect"))
    )
    (net (code "52") (name "/CSI7_CLK_P") (class "Default")
      (node (ref "J10") (pin "66") (pinfunction "66_66") (pintype "passive+no_connect"))
    )
    (net (code "53") (name "/CSI7_D0_N") (class "Default")
      (node (ref "J10") (pin "62") (pinfunction "62_62") (pintype "passive+no_connect"))
    )
    (net (code "54") (name "/CSI7_D0_P") (class "Default")
      (node (ref "J10") (pin "60") (pinfunction "60_60") (pintype "passive+no_connect"))
    )
    (net (code "55") (name "/CSI7_D1_N") (class "Default")
      (node (ref "J10") (pin "74") (pinfunction "74_74") (pintype "passive+no_connect"))
    )
    (net (code "56") (name "/CSI7_D1_P") (class "Default")
      (node (ref "J10") (pin "72") (pinfunction "72_72") (pintype "passive+no_connect"))
    )
    (net (code "57") (name "/EXT-GPIO0-I2C-SCL-A") (class "Default")
      (node (ref "J4") (pin "1") (pinfunction "1_1") (pintype "passive"))
      (node (ref "J6") (pin "2") (pinfunction "2S_2") (pintype "passive"))
      (node (ref "R15") (pin "1") (pinfunction "1_1") (pintype "passive"))
    )
    (net (code "58") (name "/EXT-GPIO0-I2C-SCL-B") (class "Default")
      (node (ref "J3") (pin "1") (pinfunction "1_1") (pintype "passive"))
      (node (ref "J5") (pin "2") (pinfunction "2S_2") (pintype "passive"))
      (node (ref "R7") (pin "1") (pinfunction "1_1") (pintype "passive"))
    )
    (net (code "59") (name "/EXT-GPIO1-I2C-SDA-A") (class "Default")
      (node (ref "J4") (pin "3") (pinfunction "3_3") (pintype "passive"))
      (node (ref "J6") (pin "3") (pinfunction "3S_3") (pintype "passive"))
      (node (ref "R16") (pin "1") (pinfunction "1_1") (pintype "passive"))
    )
    (net (code "60") (name "/EXT-GPIO1-I2C-SDA-B") (class "Default")
      (node (ref "J3") (pin "3") (pinfunction "3_3") (pintype "passive"))
      (node (ref "J5") (pin "3") (pinfunction "3S_3") (pintype "passive"))
      (node (ref "R8") (pin "1") (pinfunction "1_1") (pintype "passive"))
    )
    (net (code "61") (name "/EXT-GPIO2-A") (class "Default")
      (node (ref "J2") (pin "1") (pinfunction "1_1") (pintype "passive"))
      (node (ref "J6") (pin "5") (pinfunction "5S_5") (pintype "passive"))
      (node (ref "R2") (pin "1") (pinfunction "1_1") (pintype "passive"))
    )
    (net (code "62") (name "/EXT-GPIO2-B") (class "Default")
      (node (ref "J1") (pin "1") (pinfunction "1_1") (pintype "passive"))
      (node (ref "J5") (pin "5") (pinfunction "5S_5") (pintype "passive"))
      (node (ref "R1") (pin "1") (pinfunction "1_1") (pintype "passive"))
    )
    (net (code "63") (name "/EXT-GPIO3-A") (class "Default")
      (node (ref "J2") (pin "3") (pinfunction "3_3") (pintype "passive"))
      (node (ref "J6") (pin "6") (pinfunction "6S_6") (pintype "passive"))
      (node (ref "R4") (pin "1") (pinfunction "1_1") (pintype "passive"))
    )
    (net (code "64") (name "/EXT-GPIO3-B") (class "Default")
      (node (ref "J1") (pin "3") (pinfunction "3_3") (pintype "passive"))
      (node (ref "J5") (pin "6") (pinfunction "6S_6") (pintype "passive"))
      (node (ref "R3") (pin "1") (pinfunction "1_1") (pintype "passive"))
    )
    (net (code "65") (name "/GPIO15_CAM1_PWDN") (class "Default")
      (node (ref "J10") (pin "90") (pinfunction "90_90") (pintype "passive"))
      (node (ref "U1") (pin "4") (pinfunction "A3_4") (pintype "bidirectional"))
    )
    (net (code "66") (name "/GPIO15_CAM1_PWDN_3V3") (class "Default")
      (node (ref "J1") (pin "2") (pinfunction "2_2") (pintype "passive"))
      (node (ref "R1") (pin "2") (pinfunction "2_2") (pintype "passive"))
      (node (ref "U1") (pin "8") (pinfunction "B3_8") (pintype "bidirectional"))
    )
    (net (code "67") (name "/GPIO16_CAM1_RST") (class "Default")
      (node (ref "J10") (pin "92") (pinfunction "92_92") (pintype "passive"))
      (node (ref "R21") (pin "1") (pinfunction "1_1") (pintype "passive"))
      (node (ref "TP6") (pin "1") (pinfunction "1_1") (pintype "passive"))
    )
    (net (code "68") (name "/GPIO25_VDD_SYS_EN") (class "Default")
      (node (ref "J10") (pin "119") (pinfunction "119_119") (pintype "passive"))
      (node (ref "TP1") (pin "1") (pinfunction "1_1") (pintype "passive"))
    )
    (net (code "69") (name "/I2C_CAM_CLK") (class "Default")
      (node (ref "J4") (pin "2") (pinfunction "2_2") (pintype "passive"))
      (node (ref "R15") (pin "2") (pinfunction "2_2") (pintype "passive"))
      (node (ref "R17") (pin "1") (pinfunction "1_1") (pintype "passive"))
      (node (ref "U3") (pin "6") (pinfunction "SCL2_6") (pintype "output"))
    )
    (net (code "70") (name "/I2C_CAM_CLK_1V8") (class "Default")
      (node (ref "J10") (pin "75") (pinfunction "75_75") (pintype "passive"))
      (node (ref "R13") (pin "2") (pinfunction "2_2") (pintype "passive"))
      (node (ref "U3") (pin "3") (pinfunction "SCL1_3") (pintype "input"))
    )
    (net (code "71") (name "/I2C_CAM_DAT") (class "Default")
      (node (ref "J4") (pin "4") (pinfunction "4_4") (pintype "passive"))
      (node (ref "R16") (pin "2") (pinfunction "2_2") (pintype "passive"))
      (node (ref "R18") (pin "1") (pinfunction "1_1") (pintype "passive"))
      (node (ref "U3") (pin "5") (pinfunction "SDA2_5") (pintype "bidirectional"))
    )
    (net (code "72") (name "/I2C_CAM_DAT_1V8") (class "Default")
      (node (ref "J10") (pin "77") (pinfunction "77_77") (pintype "passive"))
      (node (ref "R14") (pin "2") (pinfunction "2_2") (pintype "passive"))
      (node (ref "U3") (pin "4") (pinfunction "SDA1_4") (pintype "bidirectional"))
    )
    (net (code "73") (name "/I2C_GP0_CLK") (class "Default")
      (node (ref "J3") (pin "2") (pinfunction "2_2") (pintype "passive"))
      (node (ref "R10") (pin "1") (pinfunction "1_1") (pintype "passive"))
      (node (ref "R7") (pin "2") (pinfunction "2_2") (pintype "passive"))
      (node (ref "U2") (pin "6") (pinfunction "SCL2_6") (pintype "output"))
    )
    (net (code "74") (name "/I2C_GP0_CLK_1V8") (class "Default")
      (node (ref "J10") (pin "105") (pinfunction "105_105") (pintype "passive"))
      (node (ref "R5") (pin "2") (pinfunction "2_2") (pintype "passive"))
      (node (ref "U2") (pin "3") (pinfunction "SCL1_3") (pintype "input"))
    )
    (net (code "75") (name "/I2C_GP0_DAT") (class "Default")
      (node (ref "J3") (pin "4") (pinfunction "4_4") (pintype "passive"))
      (node (ref "R11") (pin "1") (pinfunction "1_1") (pintype "passive"))
      (node (ref "R8") (pin "2") (pinfunction "2_2") (pintype "passive"))
      (node (ref "U2") (pin "5") (pinfunction "SDA2_5") (pintype "bidirectional"))
    )
    (net (code "76") (name "/I2C_GP0_DAT_1V8") (class "Default")
      (node (ref "J10") (pin "107") (pinfunction "107_107") (pintype "passive"))
      (node (ref "R6") (pin "2") (pinfunction "2_2") (pintype "passive"))
      (node (ref "U2") (pin "4") (pinfunction "SDA1_4") (pintype "bidirectional"))
    )
    (net (code "77") (name "/I2C_PM_CLK_1V8") (class "Default")
      (node (ref "J10") (pin "87") (pinfunction "87_87") (pintype "passive"))
      (node (ref "TP5") (pin "1") (pinfunction "1_1") (pintype "passive"))
    )
    (net (code "78") (name "/I2C_PM_DAT_1V8") (class "Default")
      (node (ref "J10") (pin "89") (pinfunction "89_89") (pintype "passive"))
      (node (ref "TP3") (pin "1") (pinfunction "1_1") (pintype "passive"))
    )
    (net (code "79") (name "/XA_GND1") (class "Default")
      (node (ref "J10") (pin "63") (pinfunction "63_63") (pintype "passive+no_connect"))
    )
    (net (code "80") (name "/XA_GND2") (class "Default")
      (node (ref "J10") (pin "64") (pinfunction "64_64") (pintype "passive+no_connect"))
    )
    (net (code "81") (name "C-GND") (class "Default")
      (node (ref "C13") (pin "2") (pinfunction "2_2") (pintype "passive"))
      (node (ref "J9") (pin "6") (pinfunction "SH_6") (pintype "passive"))
      (node (ref "J9") (pin "7") (pinfunction "SH_7") (pintype "passive"))
      (node (ref "J9") (pin "8") (pinfunction "SH_8") (pintype "passive"))
      (node (ref "J9") (pin "9") (pinfunction "SH_9") (pintype "passive"))
      (node (ref "R27") (pin "1") (pinfunction "1_1") (pintype "passive"))
      (node (ref "X2") (pin "1") (pinfunction "1_1") (pintype "passive"))
    )
    (net (code "82") (name "GND") (class "Default")
      (node (ref "C1") (pin "2") (pinfunction "2_2") (pintype "passive"))
      (node (ref "C10") (pin "2") (pinfunction "2_2") (pintype "passive"))
      (node (ref "C11") (pin "2") (pinfunction "2_2") (pintype "passive"))
      (node (ref "C12") (pin "2") (pinfunction "2_2") (pintype "passive"))
      (node (ref "C13") (pin "1") (pinfunction "1_1") (pintype "passive"))
      (node (ref "C2") (pin "2") (pinfunction "2_2") (pintype "passive"))
      (node (ref "C3") (pin "2") (pinfunction "2_2") (pintype "passive"))
      (node (ref "C4") (pin "2") (pinfunction "2_2") (pintype "passive"))
      (node (ref "C5") (pin "2") (pinfunction "2_2") (pintype "passive"))
      (node (ref "C6") (pin "2") (pinfunction "2_2") (pintype "passive"))
      (node (ref "C7") (pin "2") (pinfunction "2_2") (pintype "passive"))
      (node (ref "C8") (pin "2") (pinfunction "2_2") (pintype "passive"))
      (node (ref "C9") (pin "2") (pinfunction "2_2") (pintype "passive"))
      (node (ref "D1") (pin "K") (pinfunction "2_K") (pintype "passive"))
      (node (ref "D2") (pin "K") (pinfunction "2_K") (pintype "passive"))
      (node (ref "D3") (pin "A") (pinfunction "A_A") (pintype "passive"))
      (node (ref "D4") (pin "A") (pinfunction "A_A") (pintype "passive"))
      (node (ref "J10") (pin "100") (pinfunction "100_100") (pintype "passive"))
      (node (ref "J10") (pin "11") (pinfunction "11_11") (pintype "passive"))
      (node (ref "J10") (pin "115") (pinfunction "115_115") (pintype "passive"))
      (node (ref "J10") (pin "116") (pinfunction "116_116") (pintype "passive"))
      (node (ref "J10") (pin "12") (pinfunction "12_12") (pintype "passive"))
      (node (ref "J10") (pin "121") (pinfunction "121_121") (pintype "passive"))
      (node (ref "J10") (pin "122") (pinfunction "122_122") (pintype "passive"))
      (node (ref "J10") (pin "123") (pinfunction "123_123") (pintype "passive"))
      (node (ref "J10") (pin "124") (pinfunction "124_124") (pintype "passive"))
      (node (ref "J10") (pin "125") (pinfunction "125_125") (pintype "passive"))
      (node (ref "J10") (pin "126") (pinfunction "126_126") (pintype "passive"))
      (node (ref "J10") (pin "127") (pinfunction "127_127") (pintype "passive"))
      (node (ref "J10") (pin "128") (pinfunction "128_128") (pintype "passive"))
      (node (ref "J10") (pin "17") (pinfunction "17_17") (pintype "passive"))
      (node (ref "J10") (pin "18") (pinfunction "18_18") (pintype "passive"))
      (node (ref "J10") (pin "23") (pinfunction "23_23") (pintype "passive"))
      (node (ref "J10") (pin "24") (pinfunction "24_24") (pintype "passive"))
      (node (ref "J10") (pin "29") (pinfunction "29_29") (pintype "passive"))
      (node (ref "J10") (pin "30") (pinfunction "30_30") (pintype "passive"))
      (node (ref "J10") (pin "35") (pinfunction "35_35") (pintype "passive"))
      (node (ref "J10") (pin "36") (pinfunction "36_36") (pintype "passive"))
      (node (ref "J10") (pin "41") (pinfunction "41_41") (pintype "passive"))
      (node (ref "J10") (pin "42") (pinfunction "42_42") (pintype "passive"))
      (node (ref "J10") (pin "47") (pinfunction "47_47") (pintype "passive"))
      (node (ref "J10") (pin "48") (pinfunction "48_48") (pintype "passive"))
      (node (ref "J10") (pin "5") (pinfunction "5_5") (pintype "passive"))
      (node (ref "J10") (pin "53") (pinfunction "53_53") (pintype "passive"))
      (node (ref "J10") (pin "54") (pinfunction "54_54") (pintype "passive"))
      (node (ref "J10") (pin "6") (pinfunction "6_6") (pintype "passive"))
      (node (ref "J10") (pin "69") (pinfunction "69_69") (pintype "passive"))
      (node (ref "J10") (pin "70") (pinfunction "70_70") (pintype "passive"))
      (node (ref "J10") (pin "79") (pinfunction "79_79") (pintype "passive"))
      (node (ref "J10") (pin "80") (pinfunction "80_80") (pintype "passive"))
      (node (ref "J10") (pin "99") (pinfunction "99_99") (pintype "passive"))
      (node (ref "J5") (pin "10") (pinfunction "10_10") (pintype "passive"))
      (node (ref "J5") (pin "13") (pinfunction "13_13") (pintype "passive"))
      (node (ref "J5") (pin "16") (pinfunction "16_16") (pintype "passive"))
      (node (ref "J5") (pin "19") (pinfunction "19_19") (pintype "passive"))
      (node (ref "J5") (pin "22") (pinfunction "22_22") (pintype "passive"))
      (node (ref "J6") (pin "10") (pinfunction "10_10") (pintype "passive"))
      (node (ref "J6") (pin "13") (pinfunction "13_13") (pintype "passive"))
      (node (ref "J6") (pin "16") (pinfunction "16_16") (pintype "passive"))
      (node (ref "J6") (pin "19") (pinfunction "19_19") (pintype "passive"))
      (node (ref "J6") (pin "22") (pinfunction "22_22") (pintype "passive"))
      (node (ref "J7") (pin "2") (pinfunction "2_2") (pintype "passive"))
      (node (ref "J9") (pin "5") (pinfunction "GND_5") (pintype "passive"))
      (node (ref "R23") (pin "1") (pinfunction "1_1") (pintype "passive"))
      (node (ref "R26") (pin "1") (pinfunction "1_1") (pintype "passive"))
      (node (ref "R27") (pin "2") (pinfunction "2_2") (pintype "passive"))
      (node (ref "U1") (pin "6") (pinfunction "GND_6") (pintype "power_in"))
      (node (ref "U2") (pin "1") (pinfunction "GND_1") (pintype "power_in"))
      (node (ref "U3") (pin "1") (pinfunction "GND_1") (pintype "power_in"))
      (node (ref "U4") (pin "5") (pinfunction "GND_5") (pintype "power_in"))
      (node (ref "U4") (pin "7") (pinfunction "(EP)GND_7") (pintype "power_in"))
      (node (ref "U5") (pin "5") (pinfunction "GND_5") (pintype "power_in"))
      (node (ref "U5") (pin "7") (pinfunction "(EP)GND_7") (pintype "power_in"))
    )
    (net (code "83") (name "Net-(D1-1)") (class "Default")
      (node (ref "D1") (pin "A") (pinfunction "1_A") (pintype "passive"))
      (node (ref "R9") (pin "2") (pinfunction "2_2") (pintype "passive"))
    )
    (net (code "84") (name "Net-(D2-1)") (class "Default")
      (node (ref "D2") (pin "A") (pinfunction "1_A") (pintype "passive"))
      (node (ref "R20") (pin "2") (pinfunction "2_2") (pintype "passive"))
    )
    (net (code "85") (name "Net-(U2-EN)") (class "Default")
      (node (ref "C4") (pin "1") (pinfunction "1_1") (pintype "passive"))
      (node (ref "R12") (pin "1") (pinfunction "1_1") (pintype "passive"))
      (node (ref "U2") (pin "7") (pinfunction "VREF2_7") (pintype "power_in"))
      (node (ref "U2") (pin "8") (pinfunction "EN_8") (pintype "input"))
    )
    (net (code "86") (name "Net-(U3-EN)") (class "Default")
      (node (ref "C6") (pin "1") (pinfunction "1_1") (pintype "passive"))
      (node (ref "R19") (pin "1") (pinfunction "1_1") (pintype "passive"))
      (node (ref "U3") (pin "7") (pinfunction "VREF2_7") (pintype "power_in"))
      (node (ref "U3") (pin "8") (pinfunction "EN_8") (pintype "input"))
    )
    (net (code "87") (name "Net-(U4-EN)") (class "Default")
      (node (ref "C7") (pin "1") (pinfunction "1_1") (pintype "passive"))
      (node (ref "R21") (pin "2") (pinfunction "2_2") (pintype "passive"))
      (node (ref "R22") (pin "1") (pinfunction "1_1") (pintype "passive"))
      (node (ref "U4") (pin "4") (pinfunction "EN_4") (pintype "input"))
    )
    (net (code "88") (name "Net-(U4-ILIM)") (class "Default")
      (node (ref "R23") (pin "2") (pinfunction "2_2") (pintype "passive"))
      (node (ref "U4") (pin "2") (pinfunction "ILIM_2") (pintype "input"))
    )
    (net (code "89") (name "Net-(U5-EN)") (class "Default")
      (node (ref "C10") (pin "1") (pinfunction "1_1") (pintype "passive"))
      (node (ref "R24") (pin "2") (pinfunction "2_2") (pintype "passive"))
      (node (ref "R25") (pin "1") (pinfunction "1_1") (pintype "passive"))
      (node (ref "U5") (pin "4") (pinfunction "EN_4") (pintype "input"))
    )
    (net (code "90") (name "Net-(U5-ILIM)") (class "Default")
      (node (ref "R26") (pin "2") (pinfunction "2_2") (pintype "passive"))
      (node (ref "U5") (pin "2") (pinfunction "ILIM_2") (pintype "input"))
    )
    (net (code "91") (name "VCC-EXT-IN") (class "Default")
      (node (ref "C11") (pin "1") (pinfunction "1_1") (pintype "passive"))
      (node (ref "C8") (pin "1") (pinfunction "1_1") (pintype "passive"))
      (node (ref "D3") (pin "K") (pinfunction "K_K") (pintype "passive"))
      (node (ref "D4") (pin "K") (pinfunction "K_K") (pintype "passive"))
      (node (ref "J7") (pin "1") (pinfunction "1_1") (pintype "passive"))
      (node (ref "J8") (pin "1") (pinfunction "1_1") (pintype "passive"))
      (node (ref "J9") (pin "1") (pinfunction "VCC_1") (pintype "passive"))
      (node (ref "R22") (pin "2") (pinfunction "2_2") (pintype "passive"))
      (node (ref "R25") (pin "2") (pinfunction "2_2") (pintype "passive"))
      (node (ref "U4") (pin "6") (pinfunction "IN_6") (pintype "power_in"))
      (node (ref "U5") (pin "6") (pinfunction "IN_6") (pintype "power_in"))
    )
    (net (code "92") (name "VCC-EXT-IN-A") (class "Default")
      (node (ref "C12") (pin "1") (pinfunction "1_1") (pintype "passive"))
      (node (ref "J6") (pin "1") (pinfunction "1_1") (pintype "passive"))
      (node (ref "J6") (pin "4") (pinfunction "4_4") (pintype "passive"))
      (node (ref "J6") (pin "7") (pinfunction "7_7") (pintype "passive"))
      (node (ref "R20") (pin "1") (pinfunction "1_1") (pintype "passive"))
      (node (ref "U5") (pin "1") (pinfunction "OUT_1") (pintype "power_in"))
    )
    (net (code "93") (name "VCC-EXT-IN-B") (class "Default")
      (node (ref "C9") (pin "1") (pinfunction "1_1") (pintype "passive"))
      (node (ref "J5") (pin "1") (pinfunction "1_1") (pintype "passive"))
      (node (ref "J5") (pin "4") (pinfunction "4_4") (pintype "passive"))
      (node (ref "J5") (pin "7") (pinfunction "7_7") (pintype "passive"))
      (node (ref "R9") (pin "1") (pinfunction "1_1") (pintype "passive"))
      (node (ref "U4") (pin "1") (pinfunction "OUT_1") (pintype "power_in"))
    )
    (net (code "94") (name "VCC1V8") (class "Default")
      (node (ref "C1") (pin "1") (pinfunction "1_1") (pintype "passive"))
      (node (ref "C3") (pin "1") (pinfunction "1_1") (pintype "passive"))
      (node (ref "C5") (pin "1") (pinfunction "1_1") (pintype "passive"))
      (node (ref "J10") (pin "102") (pinfunction "102_102") (pintype "passive"))
      (node (ref "R13") (pin "1") (pinfunction "1_1") (pintype "passive"))
      (node (ref "R14") (pin "1") (pinfunction "1_1") (pintype "passive"))
      (node (ref "R5") (pin "1") (pinfunction "1_1") (pintype "passive"))
      (node (ref "R6") (pin "1") (pinfunction "1_1") (pintype "passive"))
      (node (ref "U1") (pin "1") (pinfunction "VCCA_1") (pintype "power_in"))
      (node (ref "U1") (pin "12") (pinfunction "OE_12") (pintype "input"))
      (node (ref "U2") (pin "2") (pinfunction "VREF1_2") (pintype "power_in"))
      (node (ref "U3") (pin "2") (pinfunction "VREF1_2") (pintype "power_in"))
    )
    (net (code "95") (name "VCC2V8") (class "Default")
      (node (ref "J10") (pin "81") (pinfunction "81_81") (pintype "passive"))
      (node (ref "J10") (pin "82") (pinfunction "82_82") (pintype "passive"))
      (node (ref "J10") (pin "83") (pinfunction "83_83") (pintype "passive"))
      (node (ref "TP7") (pin "1") (pinfunction "1_1") (pintype "passive"))
    )
    (net (code "96") (name "VCC3V3") (class "Default")
      (node (ref "C2") (pin "1") (pinfunction "1_1") (pintype "passive"))
      (node (ref "J10") (pin "108") (pinfunction "108_108") (pintype "passive"))
      (node (ref "J10") (pin "110") (pinfunction "110_110") (pintype "passive"))
      (node (ref "R10") (pin "2") (pinfunction "2_2") (pintype "passive"))
      (node (ref "R11") (pin "2") (pinfunction "2_2") (pintype "passive"))
      (node (ref "R12") (pin "2") (pinfunction "2_2") (pintype "passive"))
      (node (ref "R17") (pin "2") (pinfunction "2_2") (pintype "passive"))
      (node (ref "R18") (pin "2") (pinfunction "2_2") (pintype "passive"))
      (node (ref "R19") (pin "2") (pinfunction "2_2") (pintype "passive"))
      (node (ref "U1") (pin "11") (pinfunction "VCCB_11") (pintype "power_in"))
    )
    (net (code "97") (name "XA-VCC3V3_TX2-VCC5V") (class "Default")
      (node (ref "J10") (pin "118") (pinfunction "118_118") (pintype "passive"))
      (node (ref "J10") (pin "120") (pinfunction "120_120") (pintype "passive"))
      (node (ref "J8") (pin "2") (pinfunction "2_2") (pintype "passive"))
    )
    (net (code "98") (name "unconnected-(J5-Pad23)") (class "Default")
      (node (ref "J5") (pin "23") (pinfunction "23_23") (pintype "passive+no_connect"))
    )
    (net (code "99") (name "unconnected-(J5-Pad24)") (class "Default")
      (node (ref "J5") (pin "24") (pinfunction "24_24") (pintype "passive+no_connect"))
    )
    (net (code "100") (name "unconnected-(J6-Pad23)") (class "Default")
      (node (ref "J6") (pin "23") (pinfunction "23_23") (pintype "passive+no_connect"))
    )
    (net (code "101") (name "unconnected-(J6-Pad24)") (class "Default")
      (node (ref "J6") (pin "24") (pinfunction "24_24") (pintype "passive+no_connect"))
    )
    (net (code "102") (name "unconnected-(J9-D+-Pad3)") (class "Default")
      (node (ref "J9") (pin "3") (pinfunction "D+_3") (pintype "passive+no_connect"))
    )
    (net (code "103") (name "unconnected-(J9-D--Pad2)") (class "Default")
      (node (ref "J9") (pin "2") (pinfunction "D-_2") (pintype "passive+no_connect"))
    )
    (net (code "104") (name "unconnected-(J9-ID-Pad4)") (class "Default")
      (node (ref "J9") (pin "4") (pinfunction "ID_4") (pintype "passive+no_connect"))
    )
    (net (code "105") (name "unconnected-(J10-Pad55)") (class "Default")
      (node (ref "J10") (pin "55") (pinfunction "55_55") (pintype "passive+no_connect"))
    )
    (net (code "106") (name "unconnected-(J10-Pad56)") (class "Default")
      (node (ref "J10") (pin "56") (pinfunction "56_56") (pintype "passive+no_connect"))
    )
    (net (code "107") (name "unconnected-(J10-Pad57)") (class "Default")
      (node (ref "J10") (pin "57") (pinfunction "57_57") (pintype "passive+no_connect"))
    )
    (net (code "108") (name "unconnected-(J10-Pad58)") (class "Default")
      (node (ref "J10") (pin "58") (pinfunction "58_58") (pintype "passive+no_connect"))
    )
    (net (code "109") (name "unconnected-(J10-Pad76)") (class "Default")
      (node (ref "J10") (pin "76") (pinfunction "76_76") (pintype "passive+no_connect"))
    )
    (net (code "110") (name "unconnected-(J10-Pad78)") (class "Default")
      (node (ref "J10") (pin "78") (pinfunction "78_78") (pintype "passive+no_connect"))
    )
    (net (code "111") (name "unconnected-(J10-Pad84)") (class "Default")
      (node (ref "J10") (pin "84") (pinfunction "84_84") (pintype "passive+no_connect"))
    )
    (net (code "112") (name "unconnected-(J10-Pad85)") (class "Default")
      (node (ref "J10") (pin "85") (pinfunction "85_85") (pintype "passive+no_connect"))
    )
    (net (code "113") (name "unconnected-(J10-Pad86)") (class "Default")
      (node (ref "J10") (pin "86") (pinfunction "86_86") (pintype "passive+no_connect"))
    )
    (net (code "114") (name "unconnected-(J10-Pad96)") (class "Default")
      (node (ref "J10") (pin "96") (pinfunction "96_96") (pintype "passive+no_connect"))
    )
    (net (code "115") (name "unconnected-(J10-Pad97)") (class "Default")
      (node (ref "J10") (pin "97") (pinfunction "97_97") (pintype "passive+no_connect"))
    )
    (net (code "116") (name "unconnected-(J10-Pad98)") (class "Default")
      (node (ref "J10") (pin "98") (pinfunction "98_98") (pintype "passive+no_connect"))
    )
    (net (code "117") (name "unconnected-(J10-Pad101)") (class "Default")
      (node (ref "J10") (pin "101") (pinfunction "101_101") (pintype "passive+no_connect"))
    )
    (net (code "118") (name "unconnected-(J10-Pad103)") (class "Default")
      (node (ref "J10") (pin "103") (pinfunction "103_103") (pintype "passive+no_connect"))
    )
    (net (code "119") (name "unconnected-(J10-Pad104)") (class "Default")
      (node (ref "J10") (pin "104") (pinfunction "104_104") (pintype "passive+no_connect"))
    )
    (net (code "120") (name "unconnected-(J10-Pad106)") (class "Default")
      (node (ref "J10") (pin "106") (pinfunction "106_106") (pintype "passive+no_connect"))
    )
    (net (code "121") (name "unconnected-(J10-Pad109)") (class "Default")
      (node (ref "J10") (pin "109") (pinfunction "109_109") (pintype "passive+no_connect"))
    )
    (net (code "122") (name "unconnected-(J10-Pad111)") (class "Default")
      (node (ref "J10") (pin "111") (pinfunction "111_111") (pintype "passive+no_connect"))
    )
    (net (code "123") (name "unconnected-(J10-Pad112)") (class "Default")
      (node (ref "J10") (pin "112") (pinfunction "112_112") (pintype "passive+no_connect"))
    )
    (net (code "124") (name "unconnected-(J10-Pad113)") (class "Default")
      (node (ref "J10") (pin "113") (pinfunction "113_113") (pintype "passive+no_connect"))
    )
    (net (code "125") (name "unconnected-(J10-Pad114)") (class "Default")
      (node (ref "J10") (pin "114") (pinfunction "114_114") (pintype "passive+no_connect"))
    )
    (net (code "126") (name "unconnected-(J10-Pad117)") (class "Default")
      (node (ref "J10") (pin "117") (pinfunction "117_117") (pintype "passive+no_connect"))
    )
    (net (code "127") (name "unconnected-(U4-~{FAULT}-Pad3)") (class "Default")
      (node (ref "U4") (pin "3") (pinfunction "~{FAULT}_3") (pintype "output+no_connect"))
    )
    (net (code "128") (name "unconnected-(U5-~{FAULT}-Pad3)") (class "Default")
      (node (ref "U5") (pin "3") (pinfunction "~{FAULT}_3") (pintype "output+no_connect"))
    )
    (net (code "129") (name "unconnected-(X1-Pad1)") (class "Default")
      (node (ref "X1") (pin "1") (pinfunction "1_1") (pintype "passive+no_connect"))
    )
  )
)
